# OutputSlice.net
KiCad netlist of a schematic drawn in EAGLE
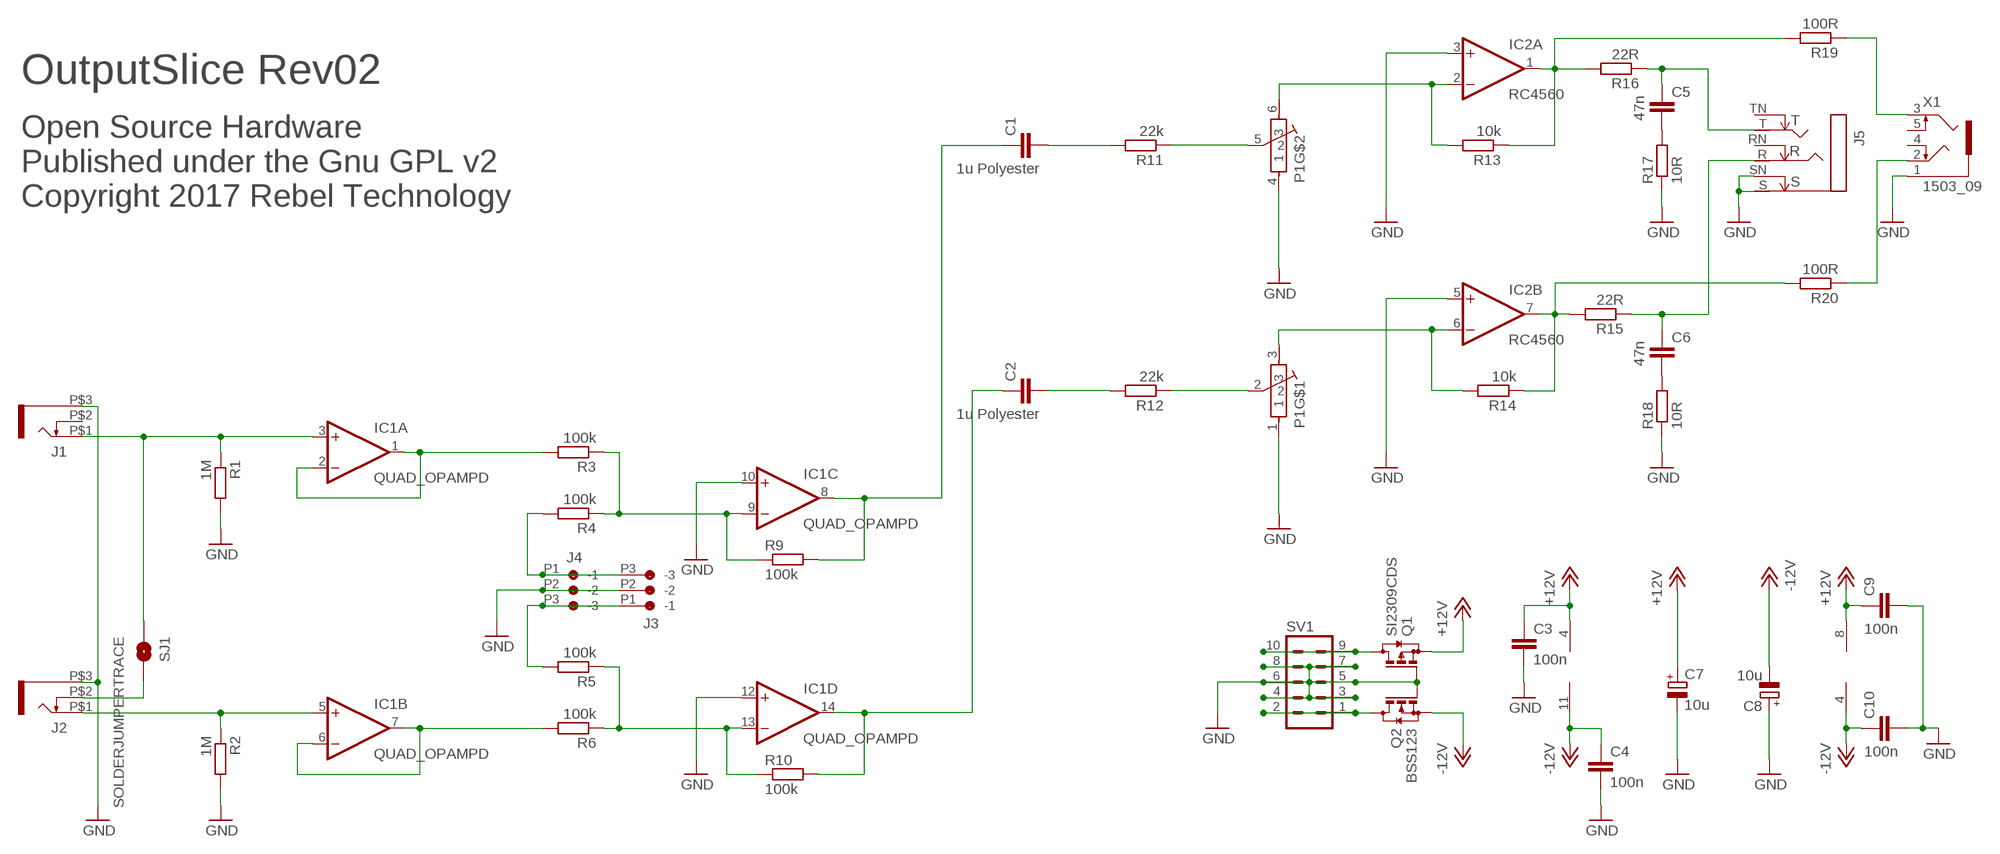
[diagram p0: schematic, sheet 1]

(export (version "E")
  (design (tool "Eeschema 10.0.6"))
  (components
    (comp (ref "C1")
      (value "1u Polyester")
      (footprint "eagle-import:C1210")
      (libsource (lib "eagle-import") (part "C-EUC1210"))
    )
    (comp (ref "C2")
      (value "1u Polyester")
      (footprint "eagle-import:C1210")
      (libsource (lib "eagle-import") (part "C-EUC1210"))
    )
    (comp (ref "C3")
      (value "100n")
      (footprint "eagle-import:C0603")
      (libsource (lib "eagle-import") (part "C-EUC0603"))
    )
    (comp (ref "C4")
      (value "100n")
      (footprint "eagle-import:C0603")
      (libsource (lib "eagle-import") (part "C-EUC0603"))
    )
    (comp (ref "C5")
      (value "47n")
      (footprint "eagle-import:C0603")
      (libsource (lib "eagle-import") (part "C-EUC0603"))
    )
    (comp (ref "C6")
      (value "47n")
      (footprint "eagle-import:C0603")
      (libsource (lib "eagle-import") (part "C-EUC0603"))
    )
    (comp (ref "C7")
      (value "10u")
      (footprint "eagle-import:153CLV-0505")
      (libsource (lib "eagle-import") (part "CPOL-EU153CLV-0505"))
    )
    (comp (ref "C8")
      (value "10u")
      (footprint "eagle-import:153CLV-0505")
      (libsource (lib "eagle-import") (part "CPOL-EU153CLV-0505"))
    )
    (comp (ref "C9")
      (value "100n")
      (footprint "eagle-import:C0603")
      (libsource (lib "eagle-import") (part "C-EUC0603"))
    )
    (comp (ref "C10")
      (value "100n")
      (footprint "eagle-import:C0603")
      (libsource (lib "eagle-import") (part "C-EUC0603"))
    )
    (comp (ref "IC1")
      (value "QUAD_OPAMPD")
      (footprint "eagle-import:SO14")
      (libsource (lib "eagle-import") (part "QUAD_OPAMPD"))
    )
    (comp (ref "IC2")
      (value "RC4560")
      (footprint "eagle-import:SO08")
      (libsource (lib "eagle-import") (part "NE5532D"))
    )
    (comp (ref "J1")
      (value "JACK-UJ-3502-RSLOT")
      (footprint "eagle-import:UJ-3502-R-SLOT")
      (libsource (lib "eagle-import") (part "JACK-UJ-3502-RSLOT"))
    )
    (comp (ref "J2")
      (value "JACK-UJ-3502-RSLOT")
      (footprint "eagle-import:UJ-3502-R-SLOT")
      (libsource (lib "eagle-import") (part "JACK-UJ-3502-RSLOT"))
    )
    (comp (ref "J3")
      (value "CON-JST_PH_3W")
      (footprint "eagle-import:CON-JST_PH_3W")
      (libsource (lib "eagle-import") (part "CON-JST_PH_3W"))
    )
    (comp (ref "J4")
      (value "CON-JST_PH_3W")
      (footprint "eagle-import:CON-JST_PH_3W")
      (libsource (lib "eagle-import") (part "CON-JST_PH_3W"))
    )
    (comp (ref "J5")
      (value "NEUTRIK_NRJ6HFSTD")
      (footprint "eagle-import:NRJ6HF")
      (libsource (lib "eagle-import") (part "NEUTRIK_NRJ6HFSTD"))
    )
    (comp (ref "P1")
      (value "POT-BOURNS-PTD902")
      (footprint "eagle-import:POT-BOURNS-PTD902")
      (libsource (lib "eagle-import") (part "POT-BOURNS-PTD902"))
    )
    (comp (ref "Q1")
      (value "SI2309CDS")
      (footprint "eagle-import:SOT23")
      (libsource (lib "eagle-import") (part "BSS84"))
    )
    (comp (ref "Q2")
      (value "BSS123")
      (footprint "eagle-import:SOT23")
      (libsource (lib "eagle-import") (part "BSS123"))
    )
    (comp (ref "R1")
      (value "1M")
      (footprint "eagle-import:0603")
      (libsource (lib "eagle-import") (part "R-EU_0603"))
    )
    (comp (ref "R2")
      (value "1M")
      (footprint "eagle-import:0603")
      (libsource (lib "eagle-import") (part "R-EU_0603"))
    )
    (comp (ref "R3")
      (value "100k")
      (footprint "eagle-import:0603")
      (libsource (lib "eagle-import") (part "R-EU_0603"))
    )
    (comp (ref "R4")
      (value "100k")
      (footprint "eagle-import:0603")
      (libsource (lib "eagle-import") (part "R-EU_0603"))
    )
    (comp (ref "R5")
      (value "100k")
      (footprint "eagle-import:0603")
      (libsource (lib "eagle-import") (part "R-EU_0603"))
    )
    (comp (ref "R6")
      (value "100k")
      (footprint "eagle-import:0603")
      (libsource (lib "eagle-import") (part "R-EU_0603"))
    )
    (comp (ref "R9")
      (value "100k")
      (footprint "eagle-import:0603")
      (libsource (lib "eagle-import") (part "R-EU_0603"))
    )
    (comp (ref "R10")
      (value "100k")
      (footprint "eagle-import:0603")
      (libsource (lib "eagle-import") (part "R-EU_0603"))
    )
    (comp (ref "R11")
      (value "22k")
      (footprint "eagle-import:0603")
      (libsource (lib "eagle-import") (part "R-EU_0603"))
    )
    (comp (ref "R12")
      (value "22k")
      (footprint "eagle-import:0603")
      (libsource (lib "eagle-import") (part "R-EU_0603"))
    )
    (comp (ref "R13")
      (value "10k")
      (footprint "eagle-import:0603")
      (libsource (lib "eagle-import") (part "R-EU_0603"))
    )
    (comp (ref "R14")
      (value "10k")
      (footprint "eagle-import:0603")
      (libsource (lib "eagle-import") (part "R-EU_0603"))
    )
    (comp (ref "R15")
      (value "22R")
      (footprint "eagle-import:0603")
      (libsource (lib "eagle-import") (part "R-EU_0603"))
    )
    (comp (ref "R16")
      (value "22R")
      (footprint "eagle-import:0603")
      (libsource (lib "eagle-import") (part "R-EU_0603"))
    )
    (comp (ref "R17")
      (value "10R")
      (footprint "eagle-import:0603")
      (libsource (lib "eagle-import") (part "R-EU_0603"))
    )
    (comp (ref "R18")
      (value "10R")
      (footprint "eagle-import:0603")
      (libsource (lib "eagle-import") (part "R-EU_0603"))
    )
    (comp (ref "R19")
      (value "100R")
      (footprint "eagle-import:0603")
      (libsource (lib "eagle-import") (part "R-EU_0603"))
    )
    (comp (ref "R20")
      (value "100R")
      (footprint "eagle-import:0603")
      (libsource (lib "eagle-import") (part "R-EU_0603"))
    )
    (comp (ref "SJ1")
      (value "SOLDERJUMPERTRACE")
      (footprint "eagle-import:SJ_2S-TRACE")
      (libsource (lib "eagle-import") (part "SOLDERJUMPERTRACE"))
    )
    (comp (ref "SV1")
      (value "MA05-2")
      (footprint "eagle-import:MA05-2")
      (libsource (lib "eagle-import") (part "MA05-2"))
    )
    (comp (ref "X1")
      (value "1503_09")
      (footprint "eagle-import:1503_09")
      (libsource (lib "eagle-import") (part "1503_09"))
    )
  )
  (nets
    (net (code "1") (name "+12V") (class "Default")
      (node (ref "C3") (pin "1") (pinfunction "1_1") (pintype "passive"))
      (node (ref "C7") (pin "+") (pinfunction "+_+") (pintype "passive"))
      (node (ref "C9") (pin "1") (pinfunction "1_1") (pintype "passive"))
      (node (ref "IC1") (pin "4") (pinfunction "V+_4") (pintype "power_in"))
      (node (ref "IC2") (pin "8") (pinfunction "V+_8") (pintype "power_in"))
      (node (ref "Q1") (pin "2") (pinfunction "S_2") (pintype "passive"))
    )
    (net (code "2") (name "-12V") (class "Default")
      (node (ref "C10") (pin "1") (pinfunction "1_1") (pintype "passive"))
      (node (ref "C4") (pin "1") (pinfunction "1_1") (pintype "passive"))
      (node (ref "C8") (pin "-") (pinfunction "-_-") (pintype "passive"))
      (node (ref "IC1") (pin "11") (pinfunction "V-_11") (pintype "power_in"))
      (node (ref "IC2") (pin "4") (pinfunction "V-_4") (pintype "power_in"))
      (node (ref "Q2") (pin "2") (pinfunction "S_2") (pintype "passive"))
    )
    (net (code "3") (name "GND") (class "Default")
      (node (ref "C10") (pin "2") (pinfunction "2_2") (pintype "passive"))
      (node (ref "C3") (pin "2") (pinfunction "2_2") (pintype "passive"))
      (node (ref "C4") (pin "2") (pinfunction "2_2") (pintype "passive"))
      (node (ref "C7") (pin "-") (pinfunction "-_-") (pintype "passive"))
      (node (ref "C8") (pin "+") (pinfunction "+_+") (pintype "passive"))
      (node (ref "C9") (pin "2") (pinfunction "2_2") (pintype "passive"))
      (node (ref "IC1") (pin "10") (pinfunction "+IN_10") (pintype "input"))
      (node (ref "IC1") (pin "12") (pinfunction "+IN_12") (pintype "input"))
      (node (ref "IC2") (pin "3") (pinfunction "+IN_3") (pintype "input"))
      (node (ref "IC2") (pin "5") (pinfunction "+IN_5") (pintype "input"))
      (node (ref "J1") (pin "P$3") (pinfunction "SLEEVE_P$3") (pintype "passive"))
      (node (ref "J2") (pin "P$3") (pinfunction "SLEEVE_P$3") (pintype "passive"))
      (node (ref "J3") (pin "P2") (pinfunction "-2_P2") (pintype "bidirectional"))
      (node (ref "J4") (pin "P2") (pinfunction "-2_P2") (pintype "bidirectional"))
      (node (ref "J5") (pin "S") (pinfunction "S_S") (pintype "passive"))
      (node (ref "J5") (pin "SN") (pinfunction "SN_SN") (pintype "passive"))
      (node (ref "P1") (pin "1") (pinfunction "1_1") (pintype "bidirectional"))
      (node (ref "P1") (pin "4") (pinfunction "1_4") (pintype "bidirectional"))
      (node (ref "Q1") (pin "1") (pinfunction "G_1") (pintype "passive"))
      (node (ref "Q2") (pin "1") (pinfunction "G_1") (pintype "passive"))
      (node (ref "R1") (pin "2") (pinfunction "2_2") (pintype "passive"))
      (node (ref "R17") (pin "1") (pinfunction "1_1") (pintype "passive"))
      (node (ref "R18") (pin "1") (pinfunction "1_1") (pintype "passive"))
      (node (ref "R2") (pin "2") (pinfunction "2_2") (pintype "passive"))
      (node (ref "SV1") (pin "3") (pinfunction "3_3") (pintype "passive"))
      (node (ref "SV1") (pin "4") (pinfunction "4_4") (pintype "passive"))
      (node (ref "SV1") (pin "5") (pinfunction "5_5") (pintype "passive"))
      (node (ref "SV1") (pin "6") (pinfunction "6_6") (pintype "passive"))
      (node (ref "SV1") (pin "7") (pinfunction "7_7") (pintype "passive"))
      (node (ref "SV1") (pin "8") (pinfunction "8_8") (pintype "passive"))
      (node (ref "X1") (pin "1") (pinfunction "1_1") (pintype "passive"))
    )
    (net (code "4") (name "Net-(C1-Pad2)") (class "Default")
      (node (ref "C1") (pin "2") (pinfunction "2_2") (pintype "passive"))
      (node (ref "R11") (pin "2") (pinfunction "2_2") (pintype "passive"))
    )
    (net (code "5") (name "Net-(C2-Pad2)") (class "Default")
      (node (ref "C2") (pin "2") (pinfunction "2_2") (pintype "passive"))
      (node (ref "R12") (pin "2") (pinfunction "2_2") (pintype "passive"))
    )
    (net (code "6") (name "Net-(C5-Pad1)") (class "Default")
      (node (ref "C5") (pin "1") (pinfunction "1_1") (pintype "passive"))
      (node (ref "J5") (pin "T") (pinfunction "T_T") (pintype "passive"))
      (node (ref "R16") (pin "1") (pinfunction "1_1") (pintype "passive"))
    )
    (net (code "7") (name "Net-(C5-Pad2)") (class "Default")
      (node (ref "C5") (pin "2") (pinfunction "2_2") (pintype "passive"))
      (node (ref "R17") (pin "2") (pinfunction "2_2") (pintype "passive"))
    )
    (net (code "8") (name "Net-(C6-Pad1)") (class "Default")
      (node (ref "C6") (pin "1") (pinfunction "1_1") (pintype "passive"))
      (node (ref "J5") (pin "R") (pinfunction "R_R") (pintype "passive"))
      (node (ref "R15") (pin "1") (pinfunction "1_1") (pintype "passive"))
    )
    (net (code "9") (name "Net-(C6-Pad2)") (class "Default")
      (node (ref "C6") (pin "2") (pinfunction "2_2") (pintype "passive"))
      (node (ref "R18") (pin "2") (pinfunction "2_2") (pintype "passive"))
    )
    (net (code "10") (name "Net-(IC1A-+IN)") (class "Default")
      (node (ref "IC1") (pin "3") (pinfunction "+IN_3") (pintype "input"))
      (node (ref "J1") (pin "P$1") (pinfunction "TIP_P$1") (pintype "passive"))
      (node (ref "R1") (pin "1") (pinfunction "1_1") (pintype "passive"))
      (node (ref "SJ1") (pin "1") (pinfunction "1_1") (pintype "passive"))
    )
    (net (code "11") (name "Net-(IC1A--IN)") (class "Default")
      (node (ref "IC1") (pin "1") (pinfunction "OUT_1") (pintype "output"))
      (node (ref "IC1") (pin "2") (pinfunction "-IN_2") (pintype "input"))
      (node (ref "R3") (pin "2") (pinfunction "2_2") (pintype "passive"))
    )
    (net (code "12") (name "Net-(IC1B-+IN)") (class "Default")
      (node (ref "IC1") (pin "5") (pinfunction "+IN_5") (pintype "input"))
      (node (ref "J2") (pin "P$1") (pinfunction "TIP_P$1") (pintype "passive"))
      (node (ref "R2") (pin "1") (pinfunction "1_1") (pintype "passive"))
    )
    (net (code "13") (name "Net-(IC1B--IN)") (class "Default")
      (node (ref "IC1") (pin "6") (pinfunction "-IN_6") (pintype "input"))
      (node (ref "IC1") (pin "7") (pinfunction "OUT_7") (pintype "output"))
      (node (ref "R6") (pin "2") (pinfunction "2_2") (pintype "passive"))
    )
    (net (code "14") (name "Net-(IC1C--IN)") (class "Default")
      (node (ref "IC1") (pin "9") (pinfunction "-IN_9") (pintype "input"))
      (node (ref "R3") (pin "1") (pinfunction "1_1") (pintype "passive"))
      (node (ref "R4") (pin "1") (pinfunction "1_1") (pintype "passive"))
      (node (ref "R9") (pin "1") (pinfunction "1_1") (pintype "passive"))
    )
    (net (code "15") (name "Net-(IC1C-OUT)") (class "Default")
      (node (ref "C1") (pin "1") (pinfunction "1_1") (pintype "passive"))
      (node (ref "IC1") (pin "8") (pinfunction "OUT_8") (pintype "output"))
      (node (ref "R9") (pin "2") (pinfunction "2_2") (pintype "passive"))
    )
    (net (code "16") (name "Net-(IC1D--IN)") (class "Default")
      (node (ref "IC1") (pin "13") (pinfunction "-IN_13") (pintype "input"))
      (node (ref "R10") (pin "1") (pinfunction "1_1") (pintype "passive"))
      (node (ref "R5") (pin "1") (pinfunction "1_1") (pintype "passive"))
      (node (ref "R6") (pin "1") (pinfunction "1_1") (pintype "passive"))
    )
    (net (code "17") (name "Net-(IC1D-OUT)") (class "Default")
      (node (ref "C2") (pin "1") (pinfunction "1_1") (pintype "passive"))
      (node (ref "IC1") (pin "14") (pinfunction "OUT_14") (pintype "output"))
      (node (ref "R10") (pin "2") (pinfunction "2_2") (pintype "passive"))
    )
    (net (code "18") (name "Net-(IC2A--IN)") (class "Default")
      (node (ref "IC2") (pin "2") (pinfunction "-IN_2") (pintype "input"))
      (node (ref "P1") (pin "6") (pinfunction "3_6") (pintype "bidirectional"))
      (node (ref "R13") (pin "2") (pinfunction "2_2") (pintype "passive"))
    )
    (net (code "19") (name "Net-(IC2A-OUT)") (class "Default")
      (node (ref "IC2") (pin "1") (pinfunction "OUT_1") (pintype "output"))
      (node (ref "R13") (pin "1") (pinfunction "1_1") (pintype "passive"))
      (node (ref "R16") (pin "2") (pinfunction "2_2") (pintype "passive"))
      (node (ref "R19") (pin "2") (pinfunction "2_2") (pintype "passive"))
    )
    (net (code "20") (name "Net-(IC2B--IN)") (class "Default")
      (node (ref "IC2") (pin "6") (pinfunction "-IN_6") (pintype "input"))
      (node (ref "P1") (pin "3") (pinfunction "3_3") (pintype "bidirectional"))
      (node (ref "R14") (pin "2") (pinfunction "2_2") (pintype "passive"))
    )
    (net (code "21") (name "Net-(IC2B-OUT)") (class "Default")
      (node (ref "IC2") (pin "7") (pinfunction "OUT_7") (pintype "output"))
      (node (ref "R14") (pin "1") (pinfunction "1_1") (pintype "passive"))
      (node (ref "R15") (pin "2") (pinfunction "2_2") (pintype "passive"))
      (node (ref "R20") (pin "2") (pinfunction "2_2") (pintype "passive"))
    )
    (net (code "22") (name "Net-(J2-SW)") (class "Default")
      (node (ref "J2") (pin "P$2") (pinfunction "SW_P$2") (pintype "passive"))
      (node (ref "SJ1") (pin "2") (pinfunction "2_2") (pintype "passive"))
    )
    (net (code "23") (name "Net-(J3--1)") (class "Default")
      (node (ref "J3") (pin "P1") (pinfunction "-1_P1") (pintype "bidirectional"))
      (node (ref "J4") (pin "P3") (pinfunction "-3_P3") (pintype "bidirectional"))
      (node (ref "R5") (pin "2") (pinfunction "2_2") (pintype "passive"))
    )
    (net (code "24") (name "Net-(J3--3)") (class "Default")
      (node (ref "J3") (pin "P3") (pinfunction "-3_P3") (pintype "bidirectional"))
      (node (ref "J4") (pin "P1") (pinfunction "-1_P1") (pintype "bidirectional"))
      (node (ref "R4") (pin "2") (pinfunction "2_2") (pintype "passive"))
    )
    (net (code "25") (name "Net-(P1-Pad2)") (class "Default")
      (node (ref "P1") (pin "2") (pinfunction "2_2") (pintype "bidirectional"))
      (node (ref "R12") (pin "1") (pinfunction "1_1") (pintype "passive"))
    )
    (net (code "26") (name "Net-(P1B-2)") (class "Default")
      (node (ref "P1") (pin "5") (pinfunction "2_5") (pintype "bidirectional"))
      (node (ref "R11") (pin "1") (pinfunction "1_1") (pintype "passive"))
    )
    (net (code "27") (name "Net-(Q1-D)") (class "Default")
      (node (ref "Q1") (pin "3") (pinfunction "D_3") (pintype "passive"))
      (node (ref "SV1") (pin "10") (pinfunction "10_10") (pintype "passive"))
      (node (ref "SV1") (pin "9") (pinfunction "9_9") (pintype "passive"))
    )
    (net (code "28") (name "Net-(Q2-D)") (class "Default")
      (node (ref "Q2") (pin "3") (pinfunction "D_3") (pintype "passive"))
      (node (ref "SV1") (pin "1") (pinfunction "1_1") (pintype "passive"))
      (node (ref "SV1") (pin "2") (pinfunction "2_2") (pintype "passive"))
    )
    (net (code "29") (name "Net-(R19-Pad1)") (class "Default")
      (node (ref "R19") (pin "1") (pinfunction "1_1") (pintype "passive"))
      (node (ref "X1") (pin "3") (pinfunction "3_3") (pintype "passive"))
    )
    (net (code "30") (name "Net-(R20-Pad1)") (class "Default")
      (node (ref "R20") (pin "1") (pinfunction "1_1") (pintype "passive"))
      (node (ref "X1") (pin "2") (pinfunction "2_2") (pintype "passive"))
    )
    (net (code "31") (name "unconnected-(J1-SW-PadP$2)") (class "Default")
      (node (ref "J1") (pin "P$2") (pinfunction "SW_P$2") (pintype "passive"))
    )
    (net (code "32") (name "unconnected-(J5-PadRN)") (class "Default")
      (node (ref "J5") (pin "RN") (pinfunction "RN_RN") (pintype "passive"))
    )
    (net (code "33") (name "unconnected-(J5-PadTN)") (class "Default")
      (node (ref "J5") (pin "TN") (pinfunction "TN_TN") (pintype "passive"))
    )
    (net (code "34") (name "unconnected-(X1-Pad4)") (class "Default")
      (node (ref "X1") (pin "4") (pinfunction "4_4") (pintype "passive"))
    )
    (net (code "35") (name "unconnected-(X1-Pad5)") (class "Default")
      (node (ref "X1") (pin "5") (pinfunction "5_5") (pintype "passive"))
    )
  )
)
